# SmartCam.net
KiCad netlist of a schematic drawn in EAGLE
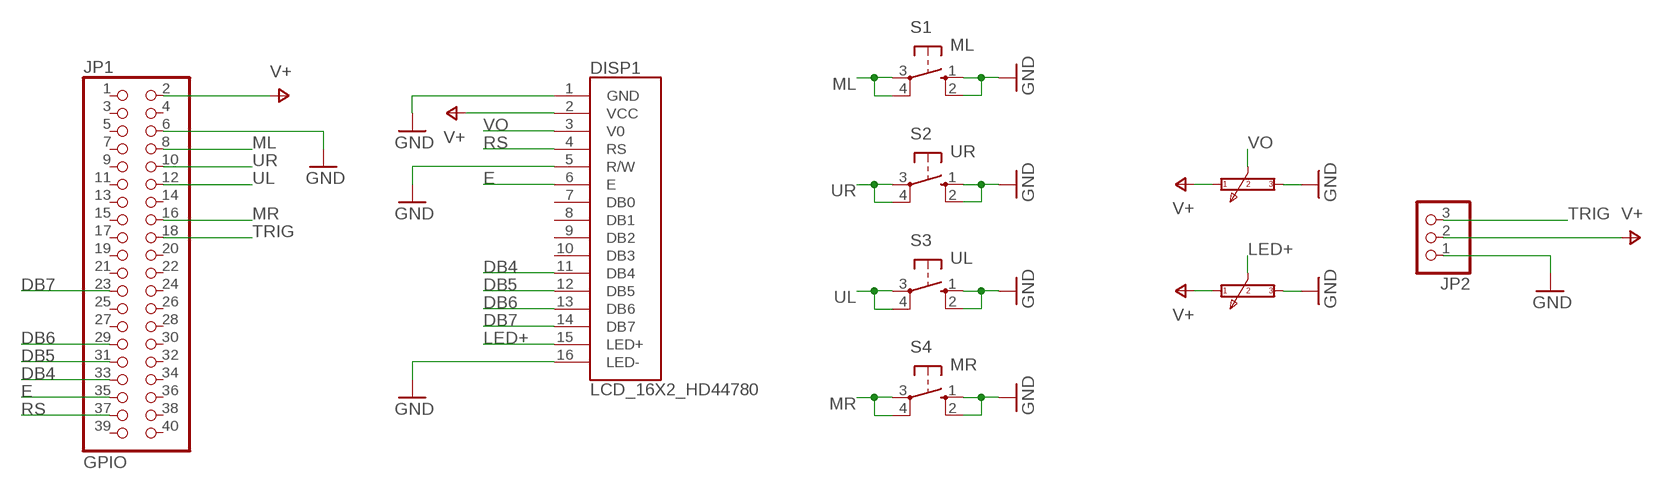
[diagram p0: schematic, sheet 1]

(export (version "E")
  (design (tool "Eeschema 10.0.6"))
  (components
    (comp (ref "DISP1")
      (value "LCD_16X2_HD44780")
      (footprint "eagle-import:LCD_16X2_HD44780")
      (libsource (lib "eagle-import") (part "LCD_16X2_HD44780"))
    )
    (comp (ref "JP1")
      (value "GPIO")
      (footprint "eagle-import:2X20")
      (libsource (lib "eagle-import") (part "PINHD-2X20"))
    )
    (comp (ref "JP2")
      (value "PINHD-1X3/90")
      (footprint "eagle-import:1X03_90")
      (libsource (lib "eagle-import") (part "PINHD-1X3/90"))
    )
    (comp (ref "POT1")
      (value "10k")
      (footprint "eagle-import:BOURNS_WEL3296_W_103")
      (libsource (lib "eagle-import") (part "BOURNS_WEL3296_W_103"))
    )
    (comp (ref "POT2")
      (value "10k")
      (footprint "eagle-import:BOURNS_WEL3296_W_103")
      (libsource (lib "eagle-import") (part "BOURNS_WEL3296_W_103"))
    )
    (comp (ref "S1")
      (value "ML")
      (footprint "eagle-import:B3F-10XX")
      (fields (field (name "MPN") "B3F-1000"))
      (libsource (lib "eagle-import") (part "10-XX"))
    )
    (comp (ref "S2")
      (value "UR")
      (footprint "eagle-import:B3F-10XX")
      (fields (field (name "MPN") "B3F-1000"))
      (libsource (lib "eagle-import") (part "10-XX"))
    )
    (comp (ref "S3")
      (value "UL")
      (footprint "eagle-import:B3F-10XX")
      (fields (field (name "MPN") "B3F-1000"))
      (libsource (lib "eagle-import") (part "10-XX"))
    )
    (comp (ref "S4")
      (value "MR")
      (footprint "eagle-import:B3F-10XX")
      (fields (field (name "MPN") "B3F-1000"))
      (libsource (lib "eagle-import") (part "10-XX"))
    )
  )
  (nets
    (net (code "1") (name "/DB4") (class "Default")
      (node (ref "DISP1") (pin "11") (pinfunction "DB4_11") (pintype "bidirectional"))
      (node (ref "JP1") (pin "33") (pinfunction "33_33") (pintype "passive"))
    )
    (net (code "2") (name "/DB5") (class "Default")
      (node (ref "DISP1") (pin "12") (pinfunction "DB5_12") (pintype "bidirectional"))
      (node (ref "JP1") (pin "31") (pinfunction "31_31") (pintype "passive"))
    )
    (net (code "3") (name "/DB6") (class "Default")
      (node (ref "DISP1") (pin "13") (pinfunction "DB6_13") (pintype "bidirectional"))
      (node (ref "JP1") (pin "29") (pinfunction "29_29") (pintype "passive"))
    )
    (net (code "4") (name "/DB7") (class "Default")
      (node (ref "DISP1") (pin "14") (pinfunction "DB7_14") (pintype "bidirectional"))
      (node (ref "JP1") (pin "23") (pinfunction "23_23") (pintype "passive"))
    )
    (net (code "5") (name "/E") (class "Default")
      (node (ref "DISP1") (pin "6") (pinfunction "E_6") (pintype "bidirectional"))
      (node (ref "JP1") (pin "35") (pinfunction "35_35") (pintype "passive"))
    )
    (net (code "6") (name "/LED+") (class "Default")
      (node (ref "DISP1") (pin "15") (pinfunction "LED+_15") (pintype "bidirectional"))
      (node (ref "POT2") (pin "P$2") (pinfunction "P$2_P$2") (pintype "bidirectional"))
    )
    (net (code "7") (name "/ML") (class "Default")
      (node (ref "JP1") (pin "8") (pinfunction "8_8") (pintype "passive"))
      (node (ref "S1") (pin "3") (pinfunction "P_3") (pintype "passive"))
      (node (ref "S1") (pin "4") (pinfunction "P1_4") (pintype "passive"))
    )
    (net (code "8") (name "/MR") (class "Default")
      (node (ref "JP1") (pin "16") (pinfunction "16_16") (pintype "passive"))
      (node (ref "S4") (pin "3") (pinfunction "P_3") (pintype "passive"))
      (node (ref "S4") (pin "4") (pinfunction "P1_4") (pintype "passive"))
    )
    (net (code "9") (name "/RS") (class "Default")
      (node (ref "DISP1") (pin "4") (pinfunction "RS_4") (pintype "bidirectional"))
      (node (ref "JP1") (pin "37") (pinfunction "37_37") (pintype "passive"))
    )
    (net (code "10") (name "/TRIG") (class "Default")
      (node (ref "JP1") (pin "18") (pinfunction "18_18") (pintype "passive"))
      (node (ref "JP2") (pin "3") (pinfunction "3_3") (pintype "passive"))
    )
    (net (code "11") (name "/UL") (class "Default")
      (node (ref "JP1") (pin "12") (pinfunction "12_12") (pintype "passive"))
      (node (ref "S3") (pin "3") (pinfunction "P_3") (pintype "passive"))
      (node (ref "S3") (pin "4") (pinfunction "P1_4") (pintype "passive"))
    )
    (net (code "12") (name "/UR") (class "Default")
      (node (ref "JP1") (pin "10") (pinfunction "10_10") (pintype "passive"))
      (node (ref "S2") (pin "3") (pinfunction "P_3") (pintype "passive"))
      (node (ref "S2") (pin "4") (pinfunction "P1_4") (pintype "passive"))
    )
    (net (code "13") (name "/VO") (class "Default")
      (node (ref "DISP1") (pin "3") (pinfunction "V0_3") (pintype "bidirectional"))
      (node (ref "POT1") (pin "P$2") (pinfunction "P$2_P$2") (pintype "bidirectional"))
    )
    (net (code "14") (name "GND") (class "Default")
      (node (ref "DISP1") (pin "1") (pinfunction "GND_1") (pintype "bidirectional"))
      (node (ref "DISP1") (pin "16") (pinfunction "LED-_16") (pintype "bidirectional"))
      (node (ref "DISP1") (pin "5") (pinfunction "R/W_5") (pintype "bidirectional"))
      (node (ref "JP1") (pin "6") (pinfunction "6_6") (pintype "passive"))
      (node (ref "JP2") (pin "1") (pinfunction "1_1") (pintype "passive"))
      (node (ref "POT1") (pin "P$3") (pinfunction "P$3_P$3") (pintype "bidirectional"))
      (node (ref "POT2") (pin "P$3") (pinfunction "P$3_P$3") (pintype "bidirectional"))
      (node (ref "S1") (pin "1") (pinfunction "S_1") (pintype "passive"))
      (node (ref "S1") (pin "2") (pinfunction "S1_2") (pintype "passive"))
      (node (ref "S2") (pin "1") (pinfunction "S_1") (pintype "passive"))
      (node (ref "S2") (pin "2") (pinfunction "S1_2") (pintype "passive"))
      (node (ref "S3") (pin "1") (pinfunction "S_1") (pintype "passive"))
      (node (ref "S3") (pin "2") (pinfunction "S1_2") (pintype "passive"))
      (node (ref "S4") (pin "1") (pinfunction "S_1") (pintype "passive"))
      (node (ref "S4") (pin "2") (pinfunction "S1_2") (pintype "passive"))
    )
    (net (code "15") (name "V+") (class "Default")
      (node (ref "DISP1") (pin "2") (pinfunction "VCC_2") (pintype "bidirectional"))
      (node (ref "JP1") (pin "2") (pinfunction "2_2") (pintype "passive"))
      (node (ref "JP2") (pin "2") (pinfunction "2_2") (pintype "passive"))
      (node (ref "POT1") (pin "P$1") (pinfunction "P$1_P$1") (pintype "bidirectional"))
      (node (ref "POT2") (pin "P$1") (pinfunction "P$1_P$1") (pintype "bidirectional"))
    )
    (net (code "16") (name "unconnected-(DISP1-DB0-Pad7)") (class "Default")
      (node (ref "DISP1") (pin "7") (pinfunction "DB0_7") (pintype "bidirectional"))
    )
    (net (code "17") (name "unconnected-(DISP1-DB1-Pad8)") (class "Default")
      (node (ref "DISP1") (pin "8") (pinfunction "DB1_8") (pintype "bidirectional"))
    )
    (net (code "18") (name "unconnected-(DISP1-DB2-Pad9)") (class "Default")
      (node (ref "DISP1") (pin "9") (pinfunction "DB2_9") (pintype "bidirectional"))
    )
    (net (code "19") (name "unconnected-(DISP1-DB3-Pad10)") (class "Default")
      (node (ref "DISP1") (pin "10") (pinfunction "DB3_10") (pintype "bidirectional"))
    )
    (net (code "20") (name "unconnected-(JP1-Pad1)") (class "Default")
      (node (ref "JP1") (pin "1") (pinfunction "1_1") (pintype "passive"))
    )
    (net (code "21") (name "unconnected-(JP1-Pad3)") (class "Default")
      (node (ref "JP1") (pin "3") (pinfunction "3_3") (pintype "passive"))
    )
    (net (code "22") (name "unconnected-(JP1-Pad4)") (class "Default")
      (node (ref "JP1") (pin "4") (pinfunction "4_4") (pintype "passive"))
    )
    (net (code "23") (name "unconnected-(JP1-Pad5)") (class "Default")
      (node (ref "JP1") (pin "5") (pinfunction "5_5") (pintype "passive"))
    )
    (net (code "24") (name "unconnected-(JP1-Pad7)") (class "Default")
      (node (ref "JP1") (pin "7") (pinfunction "7_7") (pintype "passive"))
    )
    (net (code "25") (name "unconnected-(JP1-Pad9)") (class "Default")
      (node (ref "JP1") (pin "9") (pinfunction "9_9") (pintype "passive"))
    )
    (net (code "26") (name "unconnected-(JP1-Pad11)") (class "Default")
      (node (ref "JP1") (pin "11") (pinfunction "11_11") (pintype "passive"))
    )
    (net (code "27") (name "unconnected-(JP1-Pad13)") (class "Default")
      (node (ref "JP1") (pin "13") (pinfunction "13_13") (pintype "passive"))
    )
    (net (code "28") (name "unconnected-(JP1-Pad14)") (class "Default")
      (node (ref "JP1") (pin "14") (pinfunction "14_14") (pintype "passive"))
    )
    (net (code "29") (name "unconnected-(JP1-Pad15)") (class "Default")
      (node (ref "JP1") (pin "15") (pinfunction "15_15") (pintype "passive"))
    )
    (net (code "30") (name "unconnected-(JP1-Pad17)") (class "Default")
      (node (ref "JP1") (pin "17") (pinfunction "17_17") (pintype "passive"))
    )
    (net (code "31") (name "unconnected-(JP1-Pad19)") (class "Default")
      (node (ref "JP1") (pin "19") (pinfunction "19_19") (pintype "passive"))
    )
    (net (code "32") (name "unconnected-(JP1-Pad20)") (class "Default")
      (node (ref "JP1") (pin "20") (pinfunction "20_20") (pintype "passive"))
    )
    (net (code "33") (name "unconnected-(JP1-Pad21)") (class "Default")
      (node (ref "JP1") (pin "21") (pinfunction "21_21") (pintype "passive"))
    )
    (net (code "34") (name "unconnected-(JP1-Pad22)") (class "Default")
      (node (ref "JP1") (pin "22") (pinfunction "22_22") (pintype "passive"))
    )
    (net (code "35") (name "unconnected-(JP1-Pad24)") (class "Default")
      (node (ref "JP1") (pin "24") (pinfunction "24_24") (pintype "passive"))
    )
    (net (code "36") (name "unconnected-(JP1-Pad25)") (class "Default")
      (node (ref "JP1") (pin "25") (pinfunction "25_25") (pintype "passive"))
    )
    (net (code "37") (name "unconnected-(JP1-Pad26)") (class "Default")
      (node (ref "JP1") (pin "26") (pinfunction "26_26") (pintype "passive"))
    )
    (net (code "38") (name "unconnected-(JP1-Pad27)") (class "Default")
      (node (ref "JP1") (pin "27") (pinfunction "27_27") (pintype "passive"))
    )
    (net (code "39") (name "unconnected-(JP1-Pad28)") (class "Default")
      (node (ref "JP1") (pin "28") (pinfunction "28_28") (pintype "passive"))
    )
    (net (code "40") (name "unconnected-(JP1-Pad30)") (class "Default")
      (node (ref "JP1") (pin "30") (pinfunction "30_30") (pintype "passive"))
    )
    (net (code "41") (name "unconnected-(JP1-Pad32)") (class "Default")
      (node (ref "JP1") (pin "32") (pinfunction "32_32") (pintype "passive"))
    )
    (net (code "42") (name "unconnected-(JP1-Pad34)") (class "Default")
      (node (ref "JP1") (pin "34") (pinfunction "34_34") (pintype "passive"))
    )
    (net (code "43") (name "unconnected-(JP1-Pad36)") (class "Default")
      (node (ref "JP1") (pin "36") (pinfunction "36_36") (pintype "passive"))
    )
    (net (code "44") (name "unconnected-(JP1-Pad38)") (class "Default")
      (node (ref "JP1") (pin "38") (pinfunction "38_38") (pintype "passive"))
    )
    (net (code "45") (name "unconnected-(JP1-Pad39)") (class "Default")
      (node (ref "JP1") (pin "39") (pinfunction "39_39") (pintype "passive"))
    )
    (net (code "46") (name "unconnected-(JP1-Pad40)") (class "Default")
      (node (ref "JP1") (pin "40") (pinfunction "40_40") (pintype "passive"))
    )
  )
)
